# additive_vco_hagiwo.net
KiCad netlist of a schematic drawn in EAGLE
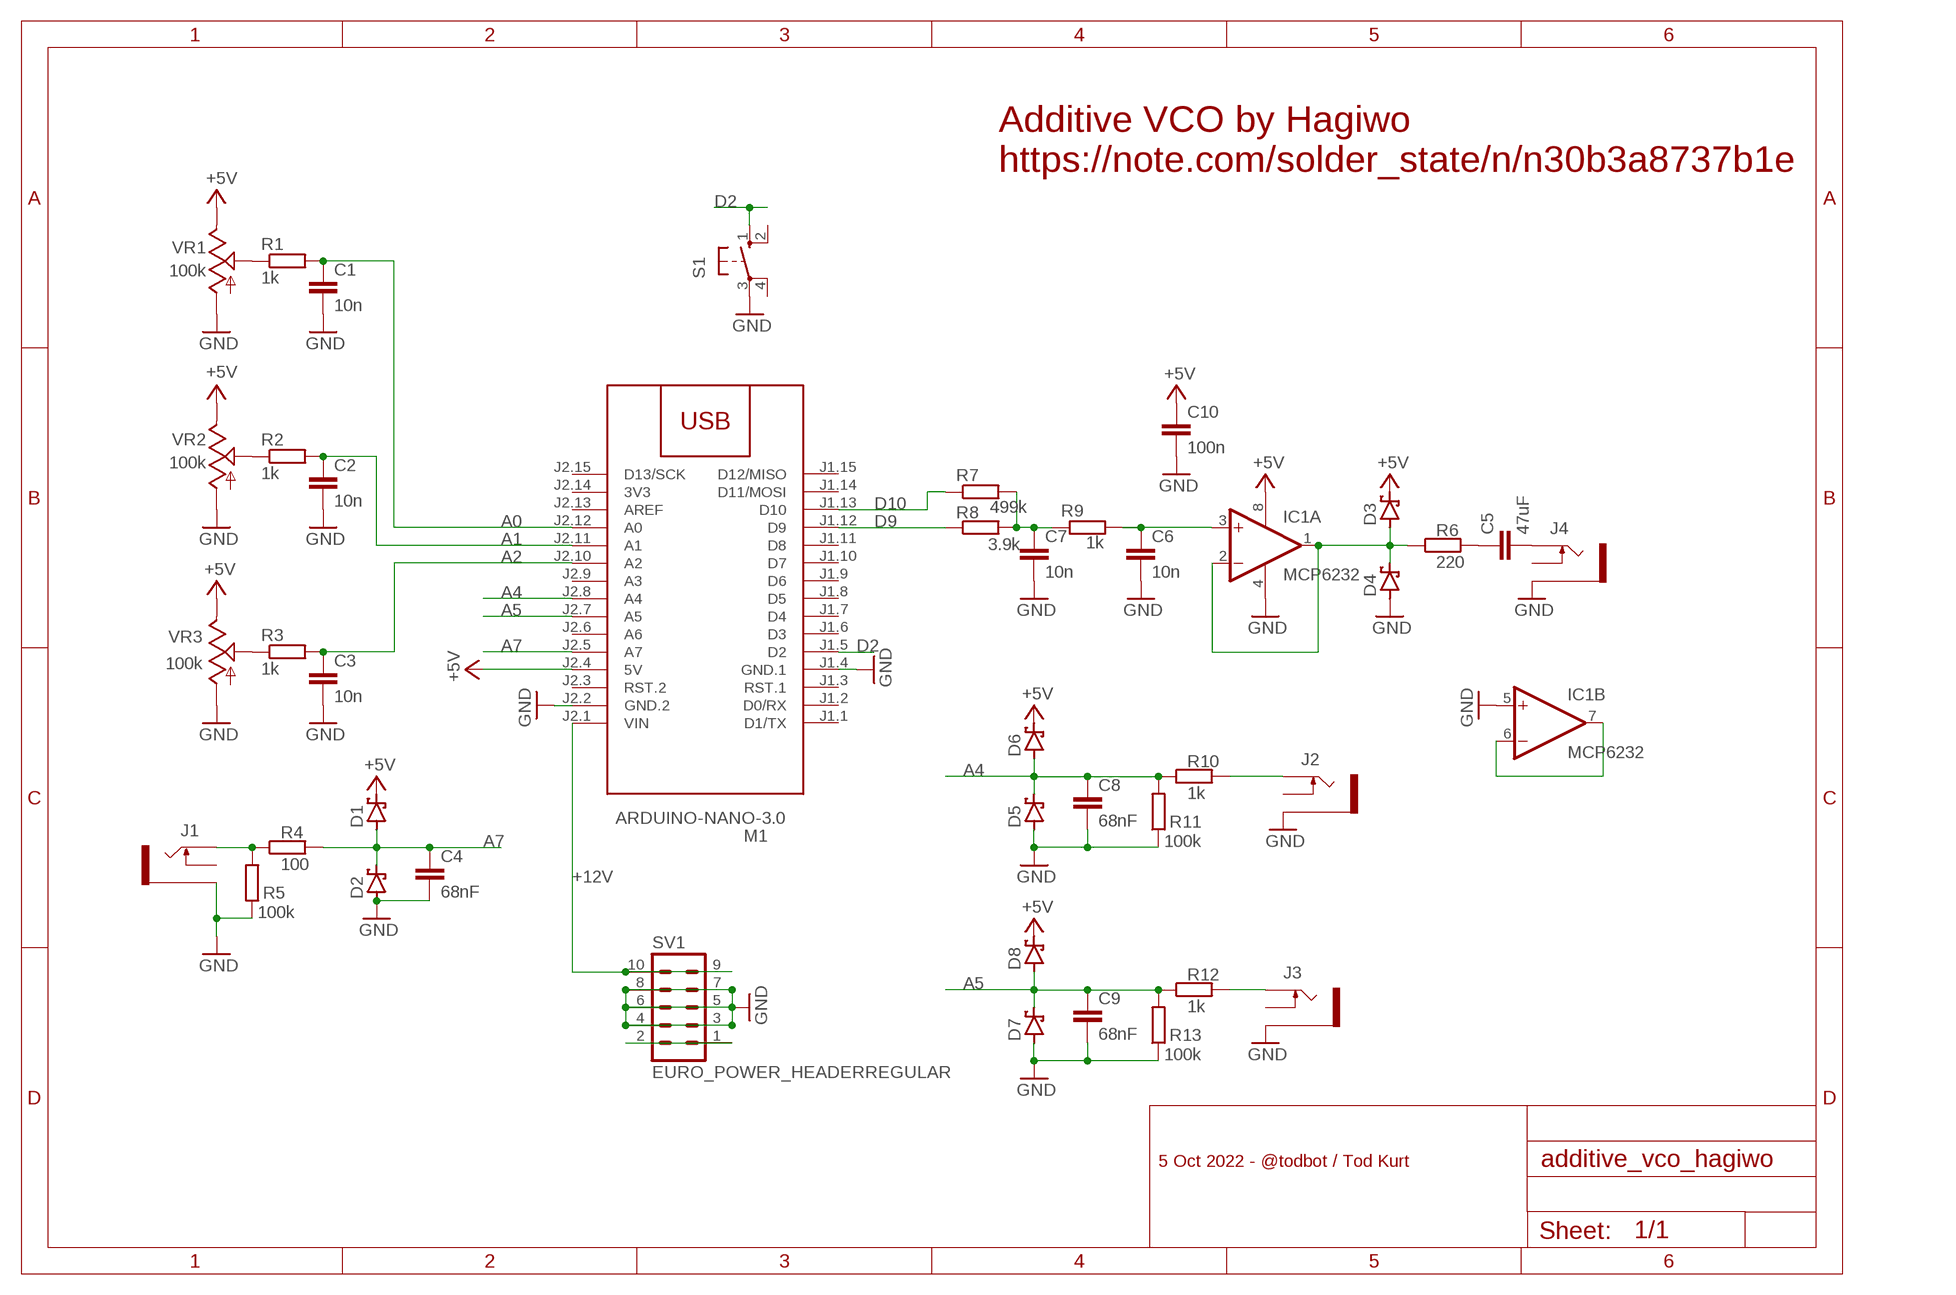
[diagram p0: schematic, sheet 1]

(export (version "E")
  (design (tool "Eeschema 10.0.6"))
  (components
    (comp (ref "C1")
      (value "10n")
      (footprint "eagle-import:C025-025X050")
      (libsource (lib "eagle-import") (part "C-EU025-025X050"))
    )
    (comp (ref "C2")
      (value "10n")
      (footprint "eagle-import:C025-025X050")
      (libsource (lib "eagle-import") (part "C-EU025-025X050"))
    )
    (comp (ref "C3")
      (value "10n")
      (footprint "eagle-import:C025-025X050")
      (libsource (lib "eagle-import") (part "C-EU025-025X050"))
    )
    (comp (ref "C4")
      (value "68nF")
      (footprint "eagle-import:C025-025X050")
      (libsource (lib "eagle-import") (part "C-EU025-025X050"))
    )
    (comp (ref "C5")
      (value "47uF")
      (footprint "eagle-import:C025-025X050")
      (libsource (lib "eagle-import") (part "C-EU025-025X050"))
    )
    (comp (ref "C6")
      (value "10n")
      (footprint "eagle-import:C025-025X050")
      (libsource (lib "eagle-import") (part "C-EU025-025X050"))
    )
    (comp (ref "C7")
      (value "10n")
      (footprint "eagle-import:C025-025X050")
      (libsource (lib "eagle-import") (part "C-EU025-025X050"))
    )
    (comp (ref "C8")
      (value "68nF")
      (footprint "eagle-import:C025-025X050")
      (libsource (lib "eagle-import") (part "C-EU025-025X050"))
    )
    (comp (ref "C9")
      (value "68nF")
      (footprint "eagle-import:C025-025X050")
      (libsource (lib "eagle-import") (part "C-EU025-025X050"))
    )
    (comp (ref "C10")
      (value "100n")
      (footprint "eagle-import:C025-025X050")
      (libsource (lib "eagle-import") (part "C-EU025-025X050"))
    )
    (comp (ref "D1")
      (value "SCHOTTKY-DIODEDO35-7")
      (footprint "eagle-import:DO35-7")
      (libsource (lib "eagle-import") (part "SCHOTTKY-DIODEDO35-7"))
    )
    (comp (ref "D2")
      (value "SCHOTTKY-DIODEDO35-7")
      (footprint "eagle-import:DO35-7")
      (libsource (lib "eagle-import") (part "SCHOTTKY-DIODEDO35-7"))
    )
    (comp (ref "D3")
      (value "SCHOTTKY-DIODEDO35-7")
      (footprint "eagle-import:DO35-7")
      (libsource (lib "eagle-import") (part "SCHOTTKY-DIODEDO35-7"))
    )
    (comp (ref "D4")
      (value "SCHOTTKY-DIODEDO35-7")
      (footprint "eagle-import:DO35-7")
      (libsource (lib "eagle-import") (part "SCHOTTKY-DIODEDO35-7"))
    )
    (comp (ref "D5")
      (value "SCHOTTKY-DIODEDO35-7")
      (footprint "eagle-import:DO35-7")
      (libsource (lib "eagle-import") (part "SCHOTTKY-DIODEDO35-7"))
    )
    (comp (ref "D6")
      (value "SCHOTTKY-DIODEDO35-7")
      (footprint "eagle-import:DO35-7")
      (libsource (lib "eagle-import") (part "SCHOTTKY-DIODEDO35-7"))
    )
    (comp (ref "D7")
      (value "SCHOTTKY-DIODEDO35-7")
      (footprint "eagle-import:DO35-7")
      (libsource (lib "eagle-import") (part "SCHOTTKY-DIODEDO35-7"))
    )
    (comp (ref "D8")
      (value "SCHOTTKY-DIODEDO35-7")
      (footprint "eagle-import:DO35-7")
      (libsource (lib "eagle-import") (part "SCHOTTKY-DIODEDO35-7"))
    )
    (comp (ref "IC1")
      (value "MCP6232")
      (footprint "eagle-import:DIL08")
      (libsource (lib "eagle-import") (part "MCP602P"))
    )
    (comp (ref "J1")
      (value "THONKICONNNEW")
      (footprint "eagle-import:WQP-PJ301M-12_JACK")
      (libsource (lib "eagle-import") (part "THONKICONNNEW"))
    )
    (comp (ref "J2")
      (value "THONKICONNNEW")
      (footprint "eagle-import:WQP-PJ301M-12_JACK")
      (libsource (lib "eagle-import") (part "THONKICONNNEW"))
    )
    (comp (ref "J3")
      (value "THONKICONNNEW")
      (footprint "eagle-import:WQP-PJ301M-12_JACK")
      (libsource (lib "eagle-import") (part "THONKICONNNEW"))
    )
    (comp (ref "J4")
      (value "THONKICONNNEW")
      (footprint "eagle-import:WQP-PJ301M-12_JACK")
      (libsource (lib "eagle-import") (part "THONKICONNNEW"))
    )
    (comp (ref "M1")
      (value "ARDUINO-NANO-3.0")
      (footprint "eagle-import:ARDUINO-NANO-3.0")
      (libsource (lib "eagle-import") (part "ARDUINO-NANO-3.0"))
    )
    (comp (ref "R1")
      (value "1k")
      (footprint "eagle-import:0204V")
      (libsource (lib "eagle-import") (part "R-EU_0204/2V"))
    )
    (comp (ref "R2")
      (value "1k")
      (footprint "eagle-import:0204V")
      (libsource (lib "eagle-import") (part "R-EU_0204/2V"))
    )
    (comp (ref "R3")
      (value "1k")
      (footprint "eagle-import:0204V")
      (libsource (lib "eagle-import") (part "R-EU_0204/2V"))
    )
    (comp (ref "R4")
      (value "100")
      (footprint "eagle-import:0204_5")
      (libsource (lib "eagle-import") (part "R-EU_0204/5"))
    )
    (comp (ref "R5")
      (value "100k")
      (footprint "eagle-import:0204_5")
      (libsource (lib "eagle-import") (part "R-EU_0204/5"))
    )
    (comp (ref "R6")
      (value "220")
      (footprint "eagle-import:0204_5")
      (libsource (lib "eagle-import") (part "R-EU_0204/5"))
    )
    (comp (ref "R7")
      (value "499k")
      (footprint "eagle-import:0204V")
      (libsource (lib "eagle-import") (part "R-EU_0204/2V"))
    )
    (comp (ref "R8")
      (value "3.9k")
      (footprint "eagle-import:0204V")
      (libsource (lib "eagle-import") (part "R-EU_0204/2V"))
    )
    (comp (ref "R9")
      (value "1k")
      (footprint "eagle-import:0204V")
      (libsource (lib "eagle-import") (part "R-EU_0204/2V"))
    )
    (comp (ref "R10")
      (value "1k")
      (footprint "eagle-import:0204_5")
      (libsource (lib "eagle-import") (part "R-EU_0204/5"))
    )
    (comp (ref "R11")
      (value "100k")
      (footprint "eagle-import:0204_5")
      (libsource (lib "eagle-import") (part "R-EU_0204/5"))
    )
    (comp (ref "R12")
      (value "1k")
      (footprint "eagle-import:0204_5")
      (libsource (lib "eagle-import") (part "R-EU_0204/5"))
    )
    (comp (ref "R13")
      (value "100k")
      (footprint "eagle-import:0204_5")
      (libsource (lib "eagle-import") (part "R-EU_0204/5"))
    )
    (comp (ref "S1")
      (value "10-XX")
      (footprint "eagle-import:B3F-10XX")
      (fields (field (name "MPN") "B3F-1000"))
      (libsource (lib "eagle-import") (part "10-XX"))
    )
    (comp (ref "SV1")
      (value "EURO_POWER_HEADERREGULAR")
      (footprint "eagle-import:EURO_POWER_HEADER")
      (libsource (lib "eagle-import") (part "EURO_POWER_HEADERREGULAR"))
    )
    (comp (ref "VR1")
      (value "100k")
      (footprint "eagle-import:9MM_SNAP-IN_POT")
      (libsource (lib "eagle-import") (part "9MM_SNAP-IN_POT_"))
    )
    (comp (ref "VR2")
      (value "100k")
      (footprint "eagle-import:9MM_SNAP-IN_POT")
      (libsource (lib "eagle-import") (part "9MM_SNAP-IN_POT_"))
    )
    (comp (ref "VR3")
      (value "100k")
      (footprint "eagle-import:9MM_SNAP-IN_POT")
      (libsource (lib "eagle-import") (part "9MM_SNAP-IN_POT_"))
    )
  )
  (nets
    (net (code "1") (name "+5V") (class "Default")
      (node (ref "C10") (pin "1") (pinfunction "1_1") (pintype "passive"))
      (node (ref "D1") (pin "C") (pinfunction "C_C") (pintype "passive"))
      (node (ref "D3") (pin "C") (pinfunction "C_C") (pintype "passive"))
      (node (ref "D6") (pin "C") (pinfunction "C_C") (pintype "passive"))
      (node (ref "D8") (pin "C") (pinfunction "C_C") (pintype "passive"))
      (node (ref "IC1") (pin "8") (pinfunction "V+_8") (pintype "power_in"))
      (node (ref "M1") (pin "J2.4") (pinfunction "5V_J2.4") (pintype "power_in"))
      (node (ref "VR1") (pin "3") (pinfunction "E_3") (pintype "passive"))
      (node (ref "VR2") (pin "3") (pinfunction "E_3") (pintype "passive"))
      (node (ref "VR3") (pin "3") (pinfunction "E_3") (pintype "passive"))
    )
    (net (code "2") (name "/+12V") (class "Default")
      (node (ref "M1") (pin "J2.1") (pinfunction "VIN_J2.1") (pintype "power_in"))
      (node (ref "SV1") (pin "10") (pinfunction "10_10") (pintype "passive"))
      (node (ref "SV1") (pin "9") (pinfunction "9_9") (pintype "passive"))
    )
    (net (code "3") (name "/3V3") (class "Default")
      (node (ref "M1") (pin "J2.14") (pinfunction "3V3_J2.14") (pintype "power_in"))
    )
    (net (code "4") (name "/A0") (class "Default")
      (node (ref "C1") (pin "1") (pinfunction "1_1") (pintype "passive"))
      (node (ref "M1") (pin "J2.12") (pinfunction "A0_J2.12") (pintype "bidirectional"))
      (node (ref "R1") (pin "2") (pinfunction "2_2") (pintype "passive"))
    )
    (net (code "5") (name "/A1") (class "Default")
      (node (ref "C2") (pin "1") (pinfunction "1_1") (pintype "passive"))
      (node (ref "M1") (pin "J2.11") (pinfunction "A1_J2.11") (pintype "bidirectional"))
      (node (ref "R2") (pin "2") (pinfunction "2_2") (pintype "passive"))
    )
    (net (code "6") (name "/A2") (class "Default")
      (node (ref "C3") (pin "1") (pinfunction "1_1") (pintype "passive"))
      (node (ref "M1") (pin "J2.10") (pinfunction "A2_J2.10") (pintype "bidirectional"))
      (node (ref "R3") (pin "2") (pinfunction "2_2") (pintype "passive"))
    )
    (net (code "7") (name "/A4") (class "Default")
      (node (ref "C8") (pin "1") (pinfunction "1_1") (pintype "passive"))
      (node (ref "D5") (pin "C") (pinfunction "C_C") (pintype "passive"))
      (node (ref "D6") (pin "A") (pinfunction "A_A") (pintype "passive"))
      (node (ref "M1") (pin "J2.8") (pinfunction "A4_J2.8") (pintype "bidirectional"))
      (node (ref "R10") (pin "1") (pinfunction "1_1") (pintype "passive"))
      (node (ref "R11") (pin "2") (pinfunction "2_2") (pintype "passive"))
    )
    (net (code "8") (name "/A5") (class "Default")
      (node (ref "C9") (pin "1") (pinfunction "1_1") (pintype "passive"))
      (node (ref "D7") (pin "C") (pinfunction "C_C") (pintype "passive"))
      (node (ref "D8") (pin "A") (pinfunction "A_A") (pintype "passive"))
      (node (ref "M1") (pin "J2.7") (pinfunction "A5_J2.7") (pintype "bidirectional"))
      (node (ref "R12") (pin "1") (pinfunction "1_1") (pintype "passive"))
      (node (ref "R13") (pin "2") (pinfunction "2_2") (pintype "passive"))
    )
    (net (code "9") (name "/A7") (class "Default")
      (node (ref "C4") (pin "1") (pinfunction "1_1") (pintype "passive"))
      (node (ref "D1") (pin "A") (pinfunction "A_A") (pintype "passive"))
      (node (ref "D2") (pin "C") (pinfunction "C_C") (pintype "passive"))
      (node (ref "M1") (pin "J2.5") (pinfunction "A7_J2.5") (pintype "bidirectional"))
      (node (ref "R4") (pin "2") (pinfunction "2_2") (pintype "passive"))
    )
    (net (code "10") (name "/D2") (class "Default")
      (node (ref "M1") (pin "J1.5") (pinfunction "D2_J1.5") (pintype "bidirectional"))
      (node (ref "S1") (pin "1") (pinfunction "S_1") (pintype "passive"))
    )
    (net (code "11") (name "/D9") (class "Default")
      (node (ref "M1") (pin "J1.12") (pinfunction "D9_J1.12") (pintype "bidirectional"))
      (node (ref "R8") (pin "1") (pinfunction "1_1") (pintype "passive"))
    )
    (net (code "12") (name "/D10") (class "Default")
      (node (ref "M1") (pin "J1.13") (pinfunction "D10_J1.13") (pintype "bidirectional"))
      (node (ref "R7") (pin "1") (pinfunction "1_1") (pintype "passive"))
    )
    (net (code "13") (name "GND") (class "Default")
      (node (ref "C1") (pin "2") (pinfunction "2_2") (pintype "passive"))
      (node (ref "C10") (pin "2") (pinfunction "2_2") (pintype "passive"))
      (node (ref "C2") (pin "2") (pinfunction "2_2") (pintype "passive"))
      (node (ref "C3") (pin "2") (pinfunction "2_2") (pintype "passive"))
      (node (ref "C4") (pin "2") (pinfunction "2_2") (pintype "passive"))
      (node (ref "C6") (pin "2") (pinfunction "2_2") (pintype "passive"))
      (node (ref "C7") (pin "2") (pinfunction "2_2") (pintype "passive"))
      (node (ref "C8") (pin "2") (pinfunction "2_2") (pintype "passive"))
      (node (ref "C9") (pin "2") (pinfunction "2_2") (pintype "passive"))
      (node (ref "D2") (pin "A") (pinfunction "A_A") (pintype "passive"))
      (node (ref "D4") (pin "A") (pinfunction "A_A") (pintype "passive"))
      (node (ref "D5") (pin "A") (pinfunction "A_A") (pintype "passive"))
      (node (ref "D7") (pin "A") (pinfunction "A_A") (pintype "passive"))
      (node (ref "IC1") (pin "4") (pinfunction "V-_4") (pintype "power_in"))
      (node (ref "IC1") (pin "5") (pinfunction "+IN_5") (pintype "input"))
      (node (ref "J1") (pin "P$3_SLEEVE") (pinfunction "SLEEVE_P$3_SLEEVE") (pintype "passive"))
      (node (ref "J2") (pin "P$3_SLEEVE") (pinfunction "SLEEVE_P$3_SLEEVE") (pintype "passive"))
      (node (ref "J3") (pin "P$3_SLEEVE") (pinfunction "SLEEVE_P$3_SLEEVE") (pintype "passive"))
      (node (ref "J4") (pin "P$3_SLEEVE") (pinfunction "SLEEVE_P$3_SLEEVE") (pintype "passive"))
      (node (ref "M1") (pin "J1.4") (pinfunction "GND.1_J1.4") (pintype "power_in"))
      (node (ref "M1") (pin "J2.2") (pinfunction "GND.2_J2.2") (pintype "power_in"))
      (node (ref "R11") (pin "1") (pinfunction "1_1") (pintype "passive"))
      (node (ref "R13") (pin "1") (pinfunction "1_1") (pintype "passive"))
      (node (ref "R5") (pin "1") (pinfunction "1_1") (pintype "passive"))
      (node (ref "S1") (pin "3") (pinfunction "P_3") (pintype "passive"))
      (node (ref "SV1") (pin "3") (pinfunction "3_3") (pintype "passive"))
      (node (ref "SV1") (pin "4") (pinfunction "4_4") (pintype "passive"))
      (node (ref "SV1") (pin "5") (pinfunction "5_5") (pintype "passive"))
      (node (ref "SV1") (pin "6") (pinfunction "6_6") (pintype "passive"))
      (node (ref "SV1") (pin "7") (pinfunction "7_7") (pintype "passive"))
      (node (ref "SV1") (pin "8") (pinfunction "8_8") (pintype "passive"))
      (node (ref "VR1") (pin "1") (pinfunction "A_1") (pintype "passive"))
      (node (ref "VR2") (pin "1") (pinfunction "A_1") (pintype "passive"))
      (node (ref "VR3") (pin "1") (pinfunction "A_1") (pintype "passive"))
    )
    (net (code "14") (name "Net-(C5-Pad1)") (class "Default")
      (node (ref "C5") (pin "1") (pinfunction "1_1") (pintype "passive"))
      (node (ref "R6") (pin "2") (pinfunction "2_2") (pintype "passive"))
    )
    (net (code "15") (name "Net-(C7-Pad1)") (class "Default")
      (node (ref "C7") (pin "1") (pinfunction "1_1") (pintype "passive"))
      (node (ref "R7") (pin "2") (pinfunction "2_2") (pintype "passive"))
      (node (ref "R8") (pin "2") (pinfunction "2_2") (pintype "passive"))
      (node (ref "R9") (pin "1") (pinfunction "1_1") (pintype "passive"))
    )
    (net (code "16") (name "Net-(IC1A-+IN)") (class "Default")
      (node (ref "C6") (pin "1") (pinfunction "1_1") (pintype "passive"))
      (node (ref "IC1") (pin "3") (pinfunction "+IN_3") (pintype "input"))
      (node (ref "R9") (pin "2") (pinfunction "2_2") (pintype "passive"))
    )
    (net (code "17") (name "Net-(IC1A--IN)") (class "Default")
      (node (ref "D3") (pin "A") (pinfunction "A_A") (pintype "passive"))
      (node (ref "D4") (pin "C") (pinfunction "C_C") (pintype "passive"))
      (node (ref "IC1") (pin "1") (pinfunction "OUT_1") (pintype "output"))
      (node (ref "IC1") (pin "2") (pinfunction "-IN_2") (pintype "input"))
      (node (ref "R6") (pin "1") (pinfunction "1_1") (pintype "passive"))
    )
    (net (code "18") (name "Net-(IC1B--IN)") (class "Default")
      (node (ref "IC1") (pin "6") (pinfunction "-IN_6") (pintype "input"))
      (node (ref "IC1") (pin "7") (pinfunction "OUT_7") (pintype "output"))
    )
    (net (code "19") (name "Net-(J1-TIP)") (class "Default")
      (node (ref "J1") (pin "P$1_TIP") (pinfunction "TIP_P$1_TIP") (pintype "passive"))
      (node (ref "R4") (pin "1") (pinfunction "1_1") (pintype "passive"))
      (node (ref "R5") (pin "2") (pinfunction "2_2") (pintype "passive"))
    )
    (net (code "20") (name "Net-(J2-TIP)") (class "Default")
      (node (ref "J2") (pin "P$1_TIP") (pinfunction "TIP_P$1_TIP") (pintype "passive"))
      (node (ref "R10") (pin "2") (pinfunction "2_2") (pintype "passive"))
    )
    (net (code "21") (name "Net-(J3-TIP)") (class "Default")
      (node (ref "J3") (pin "P$1_TIP") (pinfunction "TIP_P$1_TIP") (pintype "passive"))
      (node (ref "R12") (pin "2") (pinfunction "2_2") (pintype "passive"))
    )
    (net (code "22") (name "Net-(J4-TIP)") (class "Default")
      (node (ref "C5") (pin "2") (pinfunction "2_2") (pintype "passive"))
      (node (ref "J4") (pin "P$1_TIP") (pinfunction "TIP_P$1_TIP") (pintype "passive"))
    )
    (net (code "23") (name "Net-(SV1-Pad1)") (class "Default")
      (node (ref "SV1") (pin "1") (pinfunction "1_1") (pintype "passive"))
      (node (ref "SV1") (pin "2") (pinfunction "2_2") (pintype "passive"))
    )
    (net (code "24") (name "Net-(VR1-S)") (class "Default")
      (node (ref "R1") (pin "1") (pinfunction "1_1") (pintype "passive"))
      (node (ref "VR1") (pin "2") (pinfunction "S_2") (pintype "passive"))
    )
    (net (code "25") (name "Net-(VR2-S)") (class "Default")
      (node (ref "R2") (pin "1") (pinfunction "1_1") (pintype "passive"))
      (node (ref "VR2") (pin "2") (pinfunction "S_2") (pintype "passive"))
    )
    (net (code "26") (name "Net-(VR3-S)") (class "Default")
      (node (ref "R3") (pin "1") (pinfunction "1_1") (pintype "passive"))
      (node (ref "VR3") (pin "2") (pinfunction "S_2") (pintype "passive"))
    )
    (net (code "27") (name "unconnected-(J1-SWITCH-PadP$2_SWITCH)") (class "Default")
      (node (ref "J1") (pin "P$2_SWITCH") (pinfunction "SWITCH_P$2_SWITCH") (pintype "passive"))
    )
    (net (code "28") (name "unconnected-(J2-SWITCH-PadP$2_SWITCH)") (class "Default")
      (node (ref "J2") (pin "P$2_SWITCH") (pinfunction "SWITCH_P$2_SWITCH") (pintype "passive"))
    )
    (net (code "29") (name "unconnected-(J3-SWITCH-PadP$2_SWITCH)") (class "Default")
      (node (ref "J3") (pin "P$2_SWITCH") (pinfunction "SWITCH_P$2_SWITCH") (pintype "passive"))
    )
    (net (code "30") (name "unconnected-(J4-SWITCH-PadP$2_SWITCH)") (class "Default")
      (node (ref "J4") (pin "P$2_SWITCH") (pinfunction "SWITCH_P$2_SWITCH") (pintype "passive"))
    )
    (net (code "31") (name "unconnected-(M1-A3-PadJ2.9)") (class "Default")
      (node (ref "M1") (pin "J2.9") (pinfunction "A3_J2.9") (pintype "bidirectional"))
    )
    (net (code "32") (name "unconnected-(M1-A6-PadJ2.6)") (class "Default")
      (node (ref "M1") (pin "J2.6") (pinfunction "A6_J2.6") (pintype "bidirectional"))
    )
    (net (code "33") (name "unconnected-(M1-AREF-PadJ2.13)") (class "Default")
      (node (ref "M1") (pin "J2.13") (pinfunction "AREF_J2.13") (pintype "bidirectional"))
    )
    (net (code "34") (name "unconnected-(M1-D0{slash}RX-PadJ1.2)") (class "Default")
      (node (ref "M1") (pin "J1.2") (pinfunction "D0/RX_J1.2") (pintype "bidirectional"))
    )
    (net (code "35") (name "unconnected-(M1-D1{slash}TX-PadJ1.1)") (class "Default")
      (node (ref "M1") (pin "J1.1") (pinfunction "D1/TX_J1.1") (pintype "bidirectional"))
    )
    (net (code "36") (name "unconnected-(M1-D3-PadJ1.6)") (class "Default")
      (node (ref "M1") (pin "J1.6") (pinfunction "D3_J1.6") (pintype "bidirectional"))
    )
    (net (code "37") (name "unconnected-(M1-D4-PadJ1.7)") (class "Default")
      (node (ref "M1") (pin "J1.7") (pinfunction "D4_J1.7") (pintype "bidirectional"))
    )
    (net (code "38") (name "unconnected-(M1-D5-PadJ1.8)") (class "Default")
      (node (ref "M1") (pin "J1.8") (pinfunction "D5_J1.8") (pintype "bidirectional"))
    )
    (net (code "39") (name "unconnected-(M1-D6-PadJ1.9)") (class "Default")
      (node (ref "M1") (pin "J1.9") (pinfunction "D6_J1.9") (pintype "bidirectional"))
    )
    (net (code "40") (name "unconnected-(M1-D7-PadJ1.10)") (class "Default")
      (node (ref "M1") (pin "J1.10") (pinfunction "D7_J1.10") (pintype "bidirectional"))
    )
    (net (code "41") (name "unconnected-(M1-D8-PadJ1.11)") (class "Default")
      (node (ref "M1") (pin "J1.11") (pinfunction "D8_J1.11") (pintype "bidirectional"))
    )
    (net (code "42") (name "unconnected-(M1-D11{slash}MOSI-PadJ1.14)") (class "Default")
      (node (ref "M1") (pin "J1.14") (pinfunction "D11/MOSI_J1.14") (pintype "bidirectional"))
    )
    (net (code "43") (name "unconnected-(M1-D12{slash}MISO-PadJ1.15)") (class "Default")
      (node (ref "M1") (pin "J1.15") (pinfunction "D12/MISO_J1.15") (pintype "bidirectional"))
    )
    (net (code "44") (name "unconnected-(M1-D13{slash}SCK-PadJ2.15)") (class "Default")
      (node (ref "M1") (pin "J2.15") (pinfunction "D13/SCK_J2.15") (pintype "bidirectional"))
    )
    (net (code "45") (name "unconnected-(M1-RST.1-PadJ1.3)") (class "Default")
      (node (ref "M1") (pin "J1.3") (pinfunction "RST.1_J1.3") (pintype "bidirectional"))
    )
    (net (code "46") (name "unconnected-(M1-RST.2-PadJ2.3)") (class "Default")
      (node (ref "M1") (pin "J2.3") (pinfunction "RST.2_J2.3") (pintype "bidirectional"))
    )
    (net (code "47") (name "unconnected-(S1-P1-Pad4)") (class "Default")
      (node (ref "S1") (pin "4") (pinfunction "P1_4") (pintype "passive"))
    )
    (net (code "48") (name "unconnected-(S1-S1-Pad2)") (class "Default")
      (node (ref "S1") (pin "2") (pinfunction "S1_2") (pintype "passive"))
    )
  )
)
